# Teensy_MouseV2_0.net
KiCad netlist of a schematic drawn in EAGLE
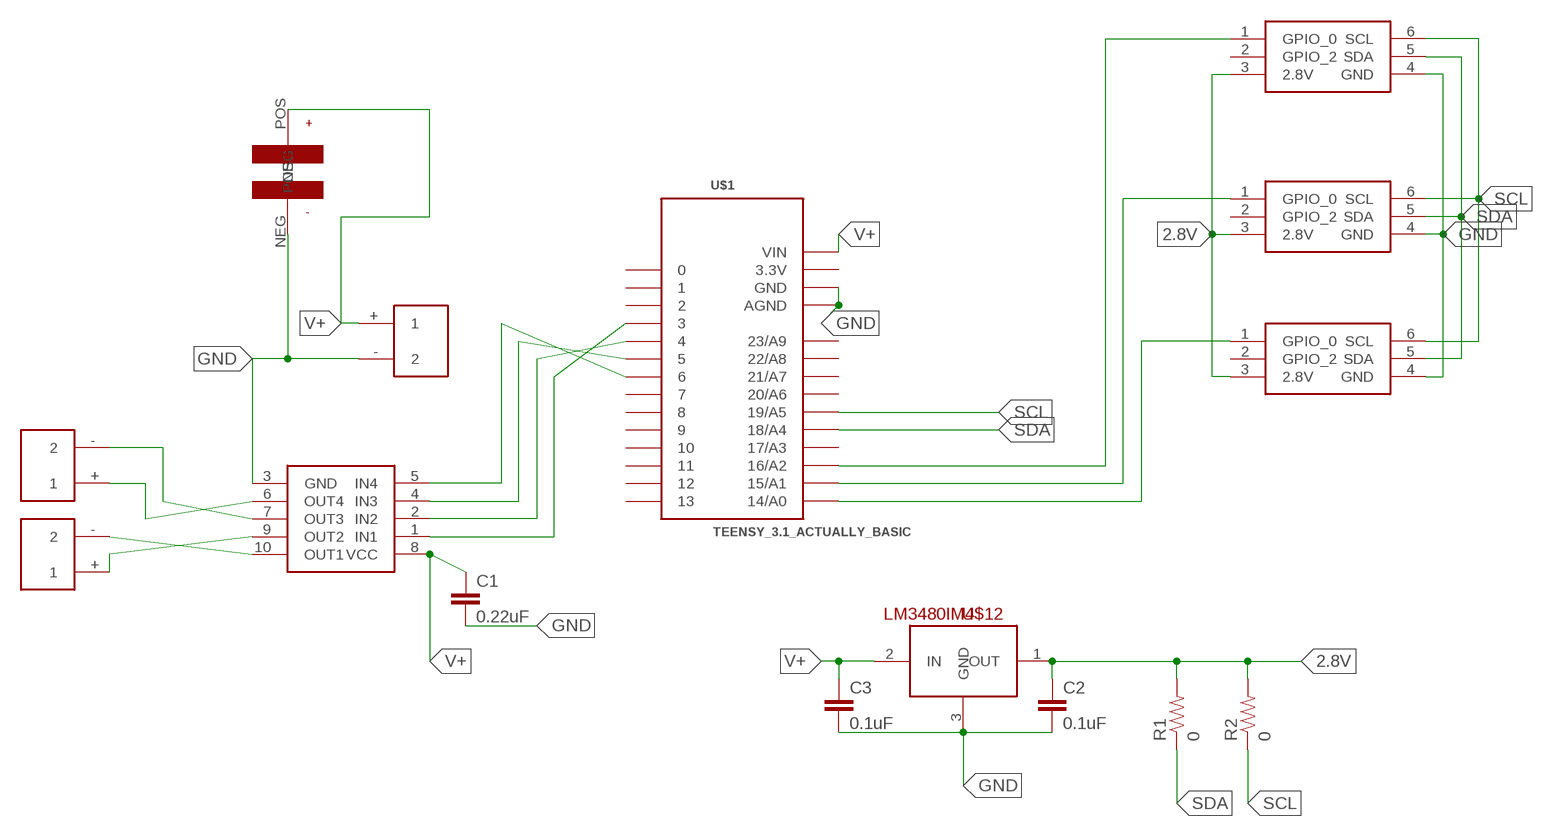
[diagram p0: schematic, sheet 1]

(export (version "E")
  (design (tool "Eeschema 10.0.6"))
  (components
    (comp (ref "C1")
      (value "0.22uF")
      (footprint "eagle-import:0603-CAP")
      (libsource (lib "eagle-import") (part "0.22UF50V-20%,+80%(0603)"))
    )
    (comp (ref "C2")
      (value "0.1uF")
      (footprint "eagle-import:0603-CAP")
      (libsource (lib "eagle-import") (part "0.1UF-25V(+80/-20%)(0603)"))
    )
    (comp (ref "C3")
      (value "0.1uF")
      (footprint "eagle-import:0603-CAP")
      (libsource (lib "eagle-import") (part "0.1UF-25V(+80/-20%)(0603)"))
    )
    (comp (ref "R1")
      (value "0")
      (footprint "eagle-import:0603")
      (libsource (lib "eagle-import") (part "0OHM1/10W5%(0603)"))
    )
    (comp (ref "R2")
      (value "0")
      (footprint "eagle-import:0603")
      (libsource (lib "eagle-import") (part "0OHM1/10W5%(0603)"))
    )
    (comp (ref "U$1")
      (value "TEENSY_3.1_ACTUALLY_BASIC")
      (footprint "eagle-import:TEENSY_3.0_ACTUALLY_BASIC")
      (libsource (lib "eagle-import") (part "TEENSY_3.1_ACTUALLY_BASIC"))
    )
    (comp (ref "U$2")
      (value "TEENSYMOUSEMOTORS")
      (footprint "eagle-import:TEENSYMOUSEMOTRS")
      (libsource (lib "eagle-import") (part "TEENSYMOUSEMOTORS"))
    )
    (comp (ref "U$3")
      (value "TEENSYMOUSEMOTORS")
      (footprint "eagle-import:TEENSYMOUSEMOTRS")
      (libsource (lib "eagle-import") (part "TEENSYMOUSEMOTORS"))
    )
    (comp (ref "U$4")
      (value "PICOBLADE2X")
      (footprint "eagle-import:PICOBLADE2X")
      (libsource (lib "eagle-import") (part "PICOBLADE2X"))
    )
    (comp (ref "U$5")
      (value "47UFBUTTONCAP")
      (footprint "eagle-import:ALUMINIUMELECTOCAP")
      (libsource (lib "eagle-import") (part "47UFBUTTONCAP"))
    )
    (comp (ref "U$7")
      (value "A3901DUALHBRIDGE")
      (footprint "eagle-import:10WFDFN")
      (libsource (lib "eagle-import") (part "A3901DUALHBRIDGE"))
    )
    (comp (ref "U$9")
      (value "PATRICK'S_ST_SENSOR_BOARD")
      (footprint "eagle-import:2X3HEADER")
      (libsource (lib "eagle-import") (part "PATRICK'S_ST_SENSOR_BOARD"))
    )
    (comp (ref "U$10")
      (value "PATRICK'S_ST_SENSOR_BOARD")
      (footprint "eagle-import:2X3HEADER")
      (libsource (lib "eagle-import") (part "PATRICK'S_ST_SENSOR_BOARD"))
    )
    (comp (ref "U$11")
      (value "PATRICK'S_ST_SENSOR_BOARD")
      (footprint "eagle-import:2X3HEADER")
      (libsource (lib "eagle-import") (part "PATRICK'S_ST_SENSOR_BOARD"))
    )
    (comp (ref "U$12")
      (value "LM3480IM4")
      (footprint "eagle-import:SOT23-3")
      (libsource (lib "eagle-import") (part "LM3480IM4"))
    )
  )
  (nets
    (net (code "1") (name "/3.3V") (class "Default")
      (node (ref "U$1") (pin "3.3V") (pinfunction "3.3V_3.3V") (pintype "power_in"))
    )
    (net (code "2") (name "2.8V") (class "Default")
      (node (ref "C2") (pin "1") (pinfunction "1_1") (pintype "passive"))
      (node (ref "R1") (pin "2") (pinfunction "2_2") (pintype "passive"))
      (node (ref "R2") (pin "2") (pinfunction "2_2") (pintype "passive"))
      (node (ref "U$10") (pin "3") (pinfunction "2.8V_3") (pintype "bidirectional"))
      (node (ref "U$11") (pin "3") (pinfunction "2.8V_3") (pintype "bidirectional"))
      (node (ref "U$12") (pin "1") (pinfunction "OUT_1") (pintype "bidirectional"))
      (node (ref "U$9") (pin "3") (pinfunction "2.8V_3") (pintype "bidirectional"))
    )
    (net (code "3") (name "GND") (class "Default")
      (node (ref "C1") (pin "2") (pinfunction "2_2") (pintype "passive"))
      (node (ref "C2") (pin "2") (pinfunction "2_2") (pintype "passive"))
      (node (ref "C3") (pin "2") (pinfunction "2_2") (pintype "passive"))
      (node (ref "U$1") (pin "AGND") (pinfunction "AGND_AGND") (pintype "power_in"))
      (node (ref "U$1") (pin "GND") (pinfunction "GND_GND") (pintype "power_in"))
      (node (ref "U$10") (pin "4") (pinfunction "GND_4") (pintype "bidirectional"))
      (node (ref "U$11") (pin "4") (pinfunction "GND_4") (pintype "bidirectional"))
      (node (ref "U$12") (pin "3") (pinfunction "GND_3") (pintype "bidirectional"))
      (node (ref "U$4") (pin "-") (pinfunction "2_-") (pintype "bidirectional"))
      (node (ref "U$5") (pin "NEG") (pinfunction "NEG_NEG") (pintype "bidirectional"))
      (node (ref "U$7") (pin "3") (pinfunction "GND_3") (pintype "bidirectional"))
      (node (ref "U$9") (pin "4") (pinfunction "GND_4") (pintype "bidirectional"))
    )
    (net (code "4") (name "Net-(U$2-1)") (class "Default")
      (node (ref "U$2") (pin "+") (pinfunction "1_+") (pintype "bidirectional"))
      (node (ref "U$7") (pin "9") (pinfunction "OUT2_9") (pintype "bidirectional"))
    )
    (net (code "5") (name "Net-(U$2-2)") (class "Default")
      (node (ref "U$2") (pin "-") (pinfunction "2_-") (pintype "bidirectional"))
      (node (ref "U$7") (pin "10") (pinfunction "OUT1_10") (pintype "bidirectional"))
    )
    (net (code "6") (name "Net-(U$3-1)") (class "Default")
      (node (ref "U$3") (pin "+") (pinfunction "1_+") (pintype "bidirectional"))
      (node (ref "U$7") (pin "6") (pinfunction "OUT4_6") (pintype "bidirectional"))
    )
    (net (code "7") (name "Net-(U$3-2)") (class "Default")
      (node (ref "U$3") (pin "-") (pinfunction "2_-") (pintype "bidirectional"))
      (node (ref "U$7") (pin "7") (pinfunction "OUT3_7") (pintype "bidirectional"))
    )
    (net (code "8") (name "Net-(U$7-IN1)") (class "Default")
      (node (ref "U$1") (pin "3") (pinfunction "3_3") (pintype "bidirectional"))
      (node (ref "U$7") (pin "1") (pinfunction "IN1_1") (pintype "bidirectional"))
    )
    (net (code "9") (name "Net-(U$7-IN2)") (class "Default")
      (node (ref "U$1") (pin "4") (pinfunction "4_4") (pintype "bidirectional"))
      (node (ref "U$7") (pin "2") (pinfunction "IN2_2") (pintype "bidirectional"))
    )
    (net (code "10") (name "Net-(U$7-IN3)") (class "Default")
      (node (ref "U$1") (pin "5") (pinfunction "5_5") (pintype "bidirectional"))
      (node (ref "U$7") (pin "4") (pinfunction "IN3_4") (pintype "bidirectional"))
    )
    (net (code "11") (name "Net-(U$7-IN4)") (class "Default")
      (node (ref "U$1") (pin "6") (pinfunction "6_6") (pintype "bidirectional"))
      (node (ref "U$7") (pin "5") (pinfunction "IN4_5") (pintype "bidirectional"))
    )
    (net (code "12") (name "Net-(U$9-GPIO_0)") (class "Default")
      (node (ref "U$1") (pin "16/A2") (pinfunction "16/A2_16/A2") (pintype "bidirectional"))
      (node (ref "U$9") (pin "1") (pinfunction "GPIO_0_1") (pintype "bidirectional"))
    )
    (net (code "13") (name "Net-(U$10-GPIO_0)") (class "Default")
      (node (ref "U$1") (pin "15/A1") (pinfunction "15/A1_15/A1") (pintype "bidirectional"))
      (node (ref "U$10") (pin "1") (pinfunction "GPIO_0_1") (pintype "bidirectional"))
    )
    (net (code "14") (name "Net-(U$11-GPIO_0)") (class "Default")
      (node (ref "U$1") (pin "14/A0") (pinfunction "14/A0_14/A0") (pintype "bidirectional"))
      (node (ref "U$11") (pin "1") (pinfunction "GPIO_0_1") (pintype "bidirectional"))
    )
    (net (code "15") (name "SCL") (class "Default")
      (node (ref "R2") (pin "1") (pinfunction "1_1") (pintype "passive"))
      (node (ref "U$1") (pin "19/A5") (pinfunction "19/A5_19/A5") (pintype "bidirectional"))
      (node (ref "U$10") (pin "6") (pinfunction "SCL_6") (pintype "bidirectional"))
      (node (ref "U$11") (pin "6") (pinfunction "SCL_6") (pintype "bidirectional"))
      (node (ref "U$9") (pin "6") (pinfunction "SCL_6") (pintype "bidirectional"))
    )
    (net (code "16") (name "SDA") (class "Default")
      (node (ref "R1") (pin "1") (pinfunction "1_1") (pintype "passive"))
      (node (ref "U$1") (pin "18/A4") (pinfunction "18/A4_18/A4") (pintype "bidirectional"))
      (node (ref "U$10") (pin "5") (pinfunction "SDA_5") (pintype "bidirectional"))
      (node (ref "U$11") (pin "5") (pinfunction "SDA_5") (pintype "bidirectional"))
      (node (ref "U$9") (pin "5") (pinfunction "SDA_5") (pintype "bidirectional"))
    )
    (net (code "17") (name "V+") (class "Default")
      (node (ref "C1") (pin "1") (pinfunction "1_1") (pintype "passive"))
      (node (ref "C3") (pin "1") (pinfunction "1_1") (pintype "passive"))
      (node (ref "U$1") (pin "VIN") (pinfunction "VIN_VIN") (pintype "power_in"))
      (node (ref "U$12") (pin "2") (pinfunction "IN_2") (pintype "bidirectional"))
      (node (ref "U$4") (pin "+") (pinfunction "1_+") (pintype "bidirectional"))
      (node (ref "U$5") (pin "POS") (pinfunction "POS_POS") (pintype "bidirectional"))
      (node (ref "U$7") (pin "8") (pinfunction "VCC_8") (pintype "bidirectional"))
    )
    (net (code "18") (name "unconnected-(U$1-Pad0)") (class "Default")
      (node (ref "U$1") (pin "0") (pinfunction "0_0") (pintype "bidirectional"))
    )
    (net (code "19") (name "unconnected-(U$1-Pad1)") (class "Default")
      (node (ref "U$1") (pin "1") (pinfunction "1_1") (pintype "bidirectional"))
    )
    (net (code "20") (name "unconnected-(U$1-Pad2)") (class "Default")
      (node (ref "U$1") (pin "2") (pinfunction "2_2") (pintype "bidirectional"))
    )
    (net (code "21") (name "unconnected-(U$1-Pad7)") (class "Default")
      (node (ref "U$1") (pin "7") (pinfunction "7_7") (pintype "bidirectional"))
    )
    (net (code "22") (name "unconnected-(U$1-Pad8)") (class "Default")
      (node (ref "U$1") (pin "8") (pinfunction "8_8") (pintype "bidirectional"))
    )
    (net (code "23") (name "unconnected-(U$1-Pad9)") (class "Default")
      (node (ref "U$1") (pin "9") (pinfunction "9_9") (pintype "bidirectional"))
    )
    (net (code "24") (name "unconnected-(U$1-Pad10)") (class "Default")
      (node (ref "U$1") (pin "10") (pinfunction "10_10") (pintype "bidirectional"))
    )
    (net (code "25") (name "unconnected-(U$1-Pad11)") (class "Default")
      (node (ref "U$1") (pin "11") (pinfunction "11_11") (pintype "bidirectional"))
    )
    (net (code "26") (name "unconnected-(U$1-Pad12)") (class "Default")
      (node (ref "U$1") (pin "12") (pinfunction "12_12") (pintype "bidirectional"))
    )
    (net (code "27") (name "unconnected-(U$1-Pad13)") (class "Default")
      (node (ref "U$1") (pin "13") (pinfunction "13_13") (pintype "bidirectional"))
    )
    (net (code "28") (name "unconnected-(U$1-Pad17{slash}A3)") (class "Default")
      (node (ref "U$1") (pin "17/A3") (pinfunction "17/A3_17/A3") (pintype "bidirectional"))
    )
    (net (code "29") (name "unconnected-(U$1-Pad20{slash}A6)") (class "Default")
      (node (ref "U$1") (pin "20/A6") (pinfunction "20/A6_20/A6") (pintype "bidirectional"))
    )
    (net (code "30") (name "unconnected-(U$1-Pad21{slash}A7)") (class "Default")
      (node (ref "U$1") (pin "21/A7") (pinfunction "21/A7_21/A7") (pintype "bidirectional"))
    )
    (net (code "31") (name "unconnected-(U$1-Pad22{slash}A8)") (class "Default")
      (node (ref "U$1") (pin "22/A8") (pinfunction "22/A8_22/A8") (pintype "bidirectional"))
    )
    (net (code "32") (name "unconnected-(U$1-Pad23{slash}A9)") (class "Default")
      (node (ref "U$1") (pin "23/A9") (pinfunction "23/A9_23/A9") (pintype "bidirectional"))
    )
    (net (code "33") (name "unconnected-(U$9-GPIO_2-Pad2)") (class "Default")
      (node (ref "U$9") (pin "2") (pinfunction "GPIO_2_2") (pintype "bidirectional"))
    )
    (net (code "34") (name "unconnected-(U$10-GPIO_2-Pad2)") (class "Default")
      (node (ref "U$10") (pin "2") (pinfunction "GPIO_2_2") (pintype "bidirectional"))
    )
    (net (code "35") (name "unconnected-(U$11-GPIO_2-Pad2)") (class "Default")
      (node (ref "U$11") (pin "2") (pinfunction "GPIO_2_2") (pintype "bidirectional"))
    )
  )
)
